# przod.net
KiCad netlist of a schematic drawn in EAGLE
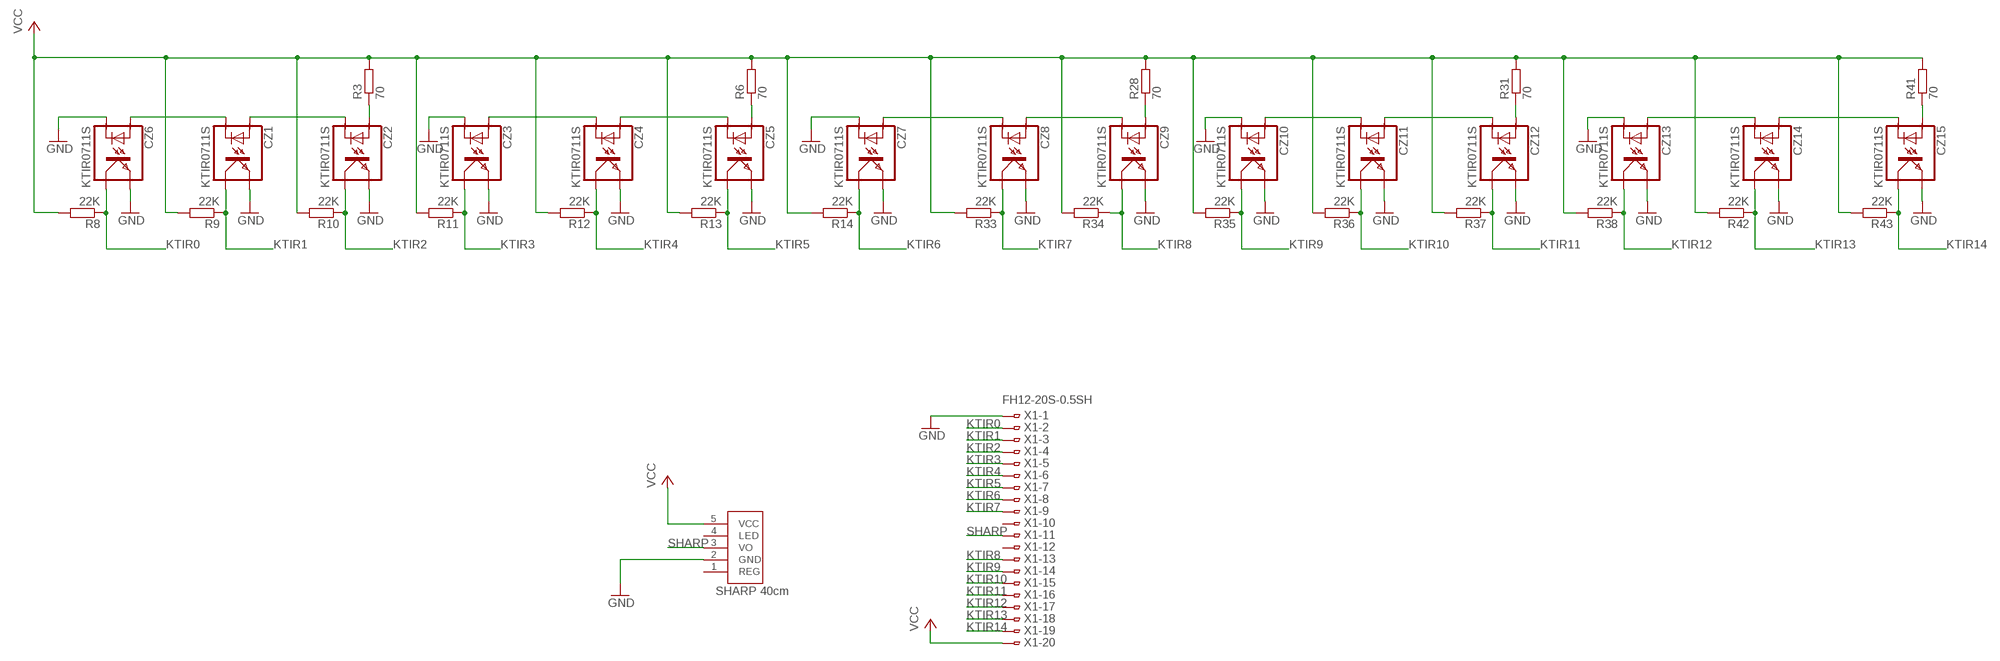
[diagram p0: schematic, sheet 1]

(export (version "E")
  (design (tool "Eeschema 10.0.6"))
  (components
    (comp (ref "CZ1")
      (value "KTIR0711S")
      (footprint "eagle-import:TOP")
      (libsource (lib "eagle-import") (part "KTIR0711S"))
    )
    (comp (ref "CZ2")
      (value "KTIR0711S")
      (footprint "eagle-import:TOP")
      (libsource (lib "eagle-import") (part "KTIR0711S"))
    )
    (comp (ref "CZ3")
      (value "KTIR0711S")
      (footprint "eagle-import:TOP")
      (libsource (lib "eagle-import") (part "KTIR0711S"))
    )
    (comp (ref "CZ4")
      (value "KTIR0711S")
      (footprint "eagle-import:TOP")
      (libsource (lib "eagle-import") (part "KTIR0711S"))
    )
    (comp (ref "CZ5")
      (value "KTIR0711S")
      (footprint "eagle-import:TOP")
      (libsource (lib "eagle-import") (part "KTIR0711S"))
    )
    (comp (ref "CZ6")
      (value "KTIR0711S")
      (footprint "eagle-import:TOP")
      (libsource (lib "eagle-import") (part "KTIR0711S"))
    )
    (comp (ref "CZ7")
      (value "KTIR0711S")
      (footprint "eagle-import:TOP")
      (libsource (lib "eagle-import") (part "KTIR0711S"))
    )
    (comp (ref "CZ8")
      (value "KTIR0711S")
      (footprint "eagle-import:TOP")
      (libsource (lib "eagle-import") (part "KTIR0711S"))
    )
    (comp (ref "CZ9")
      (value "KTIR0711S")
      (footprint "eagle-import:TOP")
      (libsource (lib "eagle-import") (part "KTIR0711S"))
    )
    (comp (ref "CZ10")
      (value "KTIR0711S")
      (footprint "eagle-import:TOP")
      (libsource (lib "eagle-import") (part "KTIR0711S"))
    )
    (comp (ref "CZ11")
      (value "KTIR0711S")
      (footprint "eagle-import:TOP")
      (libsource (lib "eagle-import") (part "KTIR0711S"))
    )
    (comp (ref "CZ12")
      (value "KTIR0711S")
      (footprint "eagle-import:TOP")
      (libsource (lib "eagle-import") (part "KTIR0711S"))
    )
    (comp (ref "CZ13")
      (value "KTIR0711S")
      (footprint "eagle-import:TOP")
      (libsource (lib "eagle-import") (part "KTIR0711S"))
    )
    (comp (ref "CZ14")
      (value "KTIR0711S")
      (footprint "eagle-import:TOP")
      (libsource (lib "eagle-import") (part "KTIR0711S"))
    )
    (comp (ref "CZ15")
      (value "KTIR0711S")
      (footprint "eagle-import:TOP")
      (libsource (lib "eagle-import") (part "KTIR0711S"))
    )
    (comp (ref "R3")
      (value "70")
      (footprint "eagle-import:R0805")
      (libsource (lib "eagle-import") (part "R-EU_R0805"))
    )
    (comp (ref "R6")
      (value "70")
      (footprint "eagle-import:R0805")
      (libsource (lib "eagle-import") (part "R-EU_R0805"))
    )
    (comp (ref "R8")
      (value "22K")
      (footprint "eagle-import:R0805")
      (libsource (lib "eagle-import") (part "R-EU_R0805"))
    )
    (comp (ref "R9")
      (value "22K")
      (footprint "eagle-import:R0805")
      (libsource (lib "eagle-import") (part "R-EU_R0805"))
    )
    (comp (ref "R10")
      (value "22K")
      (footprint "eagle-import:R0805")
      (libsource (lib "eagle-import") (part "R-EU_R0805"))
    )
    (comp (ref "R11")
      (value "22K")
      (footprint "eagle-import:R0805")
      (libsource (lib "eagle-import") (part "R-EU_R0805"))
    )
    (comp (ref "R12")
      (value "22K")
      (footprint "eagle-import:R0805")
      (libsource (lib "eagle-import") (part "R-EU_R0805"))
    )
    (comp (ref "R13")
      (value "22K")
      (footprint "eagle-import:R0805")
      (libsource (lib "eagle-import") (part "R-EU_R0805"))
    )
    (comp (ref "R14")
      (value "22K")
      (footprint "eagle-import:R0805")
      (libsource (lib "eagle-import") (part "R-EU_R0805"))
    )
    (comp (ref "R28")
      (value "70")
      (footprint "eagle-import:R0805")
      (libsource (lib "eagle-import") (part "R-EU_R0805"))
    )
    (comp (ref "R31")
      (value "70")
      (footprint "eagle-import:R0805")
      (libsource (lib "eagle-import") (part "R-EU_R0805"))
    )
    (comp (ref "R33")
      (value "22K")
      (footprint "eagle-import:R0805")
      (libsource (lib "eagle-import") (part "R-EU_R0805"))
    )
    (comp (ref "R34")
      (value "22K")
      (footprint "eagle-import:R0805")
      (libsource (lib "eagle-import") (part "R-EU_R0805"))
    )
    (comp (ref "R35")
      (value "22K")
      (footprint "eagle-import:R0805")
      (libsource (lib "eagle-import") (part "R-EU_R0805"))
    )
    (comp (ref "R36")
      (value "22K")
      (footprint "eagle-import:R0805")
      (libsource (lib "eagle-import") (part "R-EU_R0805"))
    )
    (comp (ref "R37")
      (value "22K")
      (footprint "eagle-import:R0805")
      (libsource (lib "eagle-import") (part "R-EU_R0805"))
    )
    (comp (ref "R38")
      (value "22K")
      (footprint "eagle-import:R0805")
      (libsource (lib "eagle-import") (part "R-EU_R0805"))
    )
    (comp (ref "R41")
      (value "70")
      (footprint "eagle-import:R0805")
      (libsource (lib "eagle-import") (part "R-EU_R0805"))
    )
    (comp (ref "R42")
      (value "22K")
      (footprint "eagle-import:R0805")
      (libsource (lib "eagle-import") (part "R-EU_R0805"))
    )
    (comp (ref "R43")
      (value "22K")
      (footprint "eagle-import:R0805")
      (libsource (lib "eagle-import") (part "R-EU_R0805"))
    )
    (comp (ref "U$1")
      (value "GP2Y0D340K")
      (footprint "eagle-import:GP2Y0D340K")
      (libsource (lib "eagle-import") (part "GP2Y0D340K"))
    )
    (comp (ref "X1")
      (value "FH12-20S-0.5SH")
      (footprint "eagle-import:FH12-20S-0.5SH")
      (fields (field (name "MPN") "FH12-20S-0.5SH(55)"))
      (libsource (lib "eagle-import") (part "FH12-20S-0.5SH"))
    )
  )
  (nets
    (net (code "1") (name "/KTIR0") (class "Default")
      (node (ref "CZ6") (pin "KOLEKTOR") (pinfunction "KOLEKTOR_KOLEKTOR") (pintype "bidirectional"))
      (node (ref "R8") (pin "1") (pinfunction "1_1") (pintype "passive"))
      (node (ref "X1") (pin "2") (pinfunction "1_2") (pintype "passive"))
    )
    (net (code "2") (name "/KTIR1") (class "Default")
      (node (ref "CZ1") (pin "KOLEKTOR") (pinfunction "KOLEKTOR_KOLEKTOR") (pintype "bidirectional"))
      (node (ref "R9") (pin "1") (pinfunction "1_1") (pintype "passive"))
      (node (ref "X1") (pin "3") (pinfunction "1_3") (pintype "passive"))
    )
    (net (code "3") (name "/KTIR2") (class "Default")
      (node (ref "CZ2") (pin "KOLEKTOR") (pinfunction "KOLEKTOR_KOLEKTOR") (pintype "bidirectional"))
      (node (ref "R10") (pin "1") (pinfunction "1_1") (pintype "passive"))
      (node (ref "X1") (pin "4") (pinfunction "1_4") (pintype "passive"))
    )
    (net (code "4") (name "/KTIR3") (class "Default")
      (node (ref "CZ3") (pin "KOLEKTOR") (pinfunction "KOLEKTOR_KOLEKTOR") (pintype "bidirectional"))
      (node (ref "R11") (pin "1") (pinfunction "1_1") (pintype "passive"))
      (node (ref "X1") (pin "5") (pinfunction "1_5") (pintype "passive"))
    )
    (net (code "5") (name "/KTIR4") (class "Default")
      (node (ref "CZ4") (pin "KOLEKTOR") (pinfunction "KOLEKTOR_KOLEKTOR") (pintype "bidirectional"))
      (node (ref "R12") (pin "1") (pinfunction "1_1") (pintype "passive"))
      (node (ref "X1") (pin "6") (pinfunction "1_6") (pintype "passive"))
    )
    (net (code "6") (name "/KTIR5") (class "Default")
      (node (ref "CZ5") (pin "KOLEKTOR") (pinfunction "KOLEKTOR_KOLEKTOR") (pintype "bidirectional"))
      (node (ref "R13") (pin "1") (pinfunction "1_1") (pintype "passive"))
      (node (ref "X1") (pin "7") (pinfunction "1_7") (pintype "passive"))
    )
    (net (code "7") (name "/KTIR6") (class "Default")
      (node (ref "CZ7") (pin "KOLEKTOR") (pinfunction "KOLEKTOR_KOLEKTOR") (pintype "bidirectional"))
      (node (ref "R14") (pin "1") (pinfunction "1_1") (pintype "passive"))
      (node (ref "X1") (pin "8") (pinfunction "1_8") (pintype "passive"))
    )
    (net (code "8") (name "/KTIR7") (class "Default")
      (node (ref "CZ8") (pin "KOLEKTOR") (pinfunction "KOLEKTOR_KOLEKTOR") (pintype "bidirectional"))
      (node (ref "R33") (pin "1") (pinfunction "1_1") (pintype "passive"))
      (node (ref "X1") (pin "9") (pinfunction "1_9") (pintype "passive"))
    )
    (net (code "9") (name "/KTIR8") (class "Default")
      (node (ref "CZ9") (pin "KOLEKTOR") (pinfunction "KOLEKTOR_KOLEKTOR") (pintype "bidirectional"))
      (node (ref "R34") (pin "1") (pinfunction "1_1") (pintype "passive"))
      (node (ref "X1") (pin "13") (pinfunction "1_13") (pintype "passive"))
    )
    (net (code "10") (name "/KTIR9") (class "Default")
      (node (ref "CZ10") (pin "KOLEKTOR") (pinfunction "KOLEKTOR_KOLEKTOR") (pintype "bidirectional"))
      (node (ref "R35") (pin "1") (pinfunction "1_1") (pintype "passive"))
      (node (ref "X1") (pin "14") (pinfunction "1_14") (pintype "passive"))
    )
    (net (code "11") (name "/KTIR10") (class "Default")
      (node (ref "CZ11") (pin "KOLEKTOR") (pinfunction "KOLEKTOR_KOLEKTOR") (pintype "bidirectional"))
      (node (ref "R36") (pin "1") (pinfunction "1_1") (pintype "passive"))
      (node (ref "X1") (pin "15") (pinfunction "1_15") (pintype "passive"))
    )
    (net (code "12") (name "/KTIR11") (class "Default")
      (node (ref "CZ12") (pin "KOLEKTOR") (pinfunction "KOLEKTOR_KOLEKTOR") (pintype "bidirectional"))
      (node (ref "R37") (pin "1") (pinfunction "1_1") (pintype "passive"))
      (node (ref "X1") (pin "16") (pinfunction "1_16") (pintype "passive"))
    )
    (net (code "13") (name "/KTIR12") (class "Default")
      (node (ref "CZ13") (pin "KOLEKTOR") (pinfunction "KOLEKTOR_KOLEKTOR") (pintype "bidirectional"))
      (node (ref "R38") (pin "1") (pinfunction "1_1") (pintype "passive"))
      (node (ref "X1") (pin "17") (pinfunction "1_17") (pintype "passive"))
    )
    (net (code "14") (name "/KTIR13") (class "Default")
      (node (ref "CZ14") (pin "KOLEKTOR") (pinfunction "KOLEKTOR_KOLEKTOR") (pintype "bidirectional"))
      (node (ref "R42") (pin "1") (pinfunction "1_1") (pintype "passive"))
      (node (ref "X1") (pin "18") (pinfunction "1_18") (pintype "passive"))
    )
    (net (code "15") (name "/KTIR14") (class "Default")
      (node (ref "CZ15") (pin "KOLEKTOR") (pinfunction "KOLEKTOR_KOLEKTOR") (pintype "bidirectional"))
      (node (ref "R43") (pin "1") (pinfunction "1_1") (pintype "passive"))
      (node (ref "X1") (pin "19") (pinfunction "1_19") (pintype "passive"))
    )
    (net (code "16") (name "/SHARP") (class "Default")
      (node (ref "U$1") (pin "3") (pinfunction "VO_3") (pintype "bidirectional"))
      (node (ref "X1") (pin "11") (pinfunction "1_11") (pintype "passive"))
    )
    (net (code "17") (name "GND") (class "Default")
      (node (ref "CZ1") (pin "EMITER") (pinfunction "EMITER_EMITER") (pintype "bidirectional"))
      (node (ref "CZ10") (pin "EMITER") (pinfunction "EMITER_EMITER") (pintype "bidirectional"))
      (node (ref "CZ10") (pin "KATODA") (pinfunction "KATODA_KATODA") (pintype "passive"))
      (node (ref "CZ11") (pin "EMITER") (pinfunction "EMITER_EMITER") (pintype "bidirectional"))
      (node (ref "CZ12") (pin "EMITER") (pinfunction "EMITER_EMITER") (pintype "bidirectional"))
      (node (ref "CZ13") (pin "EMITER") (pinfunction "EMITER_EMITER") (pintype "bidirectional"))
      (node (ref "CZ13") (pin "KATODA") (pinfunction "KATODA_KATODA") (pintype "passive"))
      (node (ref "CZ14") (pin "EMITER") (pinfunction "EMITER_EMITER") (pintype "bidirectional"))
      (node (ref "CZ15") (pin "EMITER") (pinfunction "EMITER_EMITER") (pintype "bidirectional"))
      (node (ref "CZ2") (pin "EMITER") (pinfunction "EMITER_EMITER") (pintype "bidirectional"))
      (node (ref "CZ3") (pin "EMITER") (pinfunction "EMITER_EMITER") (pintype "bidirectional"))
      (node (ref "CZ3") (pin "KATODA") (pinfunction "KATODA_KATODA") (pintype "passive"))
      (node (ref "CZ4") (pin "EMITER") (pinfunction "EMITER_EMITER") (pintype "bidirectional"))
      (node (ref "CZ5") (pin "EMITER") (pinfunction "EMITER_EMITER") (pintype "bidirectional"))
      (node (ref "CZ6") (pin "EMITER") (pinfunction "EMITER_EMITER") (pintype "bidirectional"))
      (node (ref "CZ6") (pin "KATODA") (pinfunction "KATODA_KATODA") (pintype "passive"))
      (node (ref "CZ7") (pin "EMITER") (pinfunction "EMITER_EMITER") (pintype "bidirectional"))
      (node (ref "CZ7") (pin "KATODA") (pinfunction "KATODA_KATODA") (pintype "passive"))
      (node (ref "CZ8") (pin "EMITER") (pinfunction "EMITER_EMITER") (pintype "bidirectional"))
      (node (ref "CZ9") (pin "EMITER") (pinfunction "EMITER_EMITER") (pintype "bidirectional"))
      (node (ref "U$1") (pin "2") (pinfunction "GND_2") (pintype "bidirectional"))
      (node (ref "X1") (pin "1") (pinfunction "1_1") (pintype "passive"))
    )
    (net (code "18") (name "Net-(CZ1-PadANODA)") (class "Default")
      (node (ref "CZ1") (pin "ANODA") (pinfunction "ANODA_ANODA") (pintype "passive"))
      (node (ref "CZ2") (pin "KATODA") (pinfunction "KATODA_KATODA") (pintype "passive"))
    )
    (net (code "19") (name "Net-(CZ1-PadKATODA)") (class "Default")
      (node (ref "CZ1") (pin "KATODA") (pinfunction "KATODA_KATODA") (pintype "passive"))
      (node (ref "CZ6") (pin "ANODA") (pinfunction "ANODA_ANODA") (pintype "passive"))
    )
    (net (code "20") (name "Net-(CZ2-PadANODA)") (class "Default")
      (node (ref "CZ2") (pin "ANODA") (pinfunction "ANODA_ANODA") (pintype "passive"))
      (node (ref "R3") (pin "1") (pinfunction "1_1") (pintype "passive"))
    )
    (net (code "21") (name "Net-(CZ3-PadANODA)") (class "Default")
      (node (ref "CZ3") (pin "ANODA") (pinfunction "ANODA_ANODA") (pintype "passive"))
      (node (ref "CZ4") (pin "KATODA") (pinfunction "KATODA_KATODA") (pintype "passive"))
    )
    (net (code "22") (name "Net-(CZ4-PadANODA)") (class "Default")
      (node (ref "CZ4") (pin "ANODA") (pinfunction "ANODA_ANODA") (pintype "passive"))
      (node (ref "CZ5") (pin "KATODA") (pinfunction "KATODA_KATODA") (pintype "passive"))
    )
    (net (code "23") (name "Net-(CZ5-PadANODA)") (class "Default")
      (node (ref "CZ5") (pin "ANODA") (pinfunction "ANODA_ANODA") (pintype "passive"))
      (node (ref "R6") (pin "1") (pinfunction "1_1") (pintype "passive"))
    )
    (net (code "24") (name "Net-(CZ7-PadANODA)") (class "Default")
      (node (ref "CZ7") (pin "ANODA") (pinfunction "ANODA_ANODA") (pintype "passive"))
      (node (ref "CZ8") (pin "KATODA") (pinfunction "KATODA_KATODA") (pintype "passive"))
    )
    (net (code "25") (name "Net-(CZ8-PadANODA)") (class "Default")
      (node (ref "CZ8") (pin "ANODA") (pinfunction "ANODA_ANODA") (pintype "passive"))
      (node (ref "CZ9") (pin "KATODA") (pinfunction "KATODA_KATODA") (pintype "passive"))
    )
    (net (code "26") (name "Net-(CZ9-PadANODA)") (class "Default")
      (node (ref "CZ9") (pin "ANODA") (pinfunction "ANODA_ANODA") (pintype "passive"))
      (node (ref "R28") (pin "1") (pinfunction "1_1") (pintype "passive"))
    )
    (net (code "27") (name "Net-(CZ10-PadANODA)") (class "Default")
      (node (ref "CZ10") (pin "ANODA") (pinfunction "ANODA_ANODA") (pintype "passive"))
      (node (ref "CZ11") (pin "KATODA") (pinfunction "KATODA_KATODA") (pintype "passive"))
    )
    (net (code "28") (name "Net-(CZ11-PadANODA)") (class "Default")
      (node (ref "CZ11") (pin "ANODA") (pinfunction "ANODA_ANODA") (pintype "passive"))
      (node (ref "CZ12") (pin "KATODA") (pinfunction "KATODA_KATODA") (pintype "passive"))
    )
    (net (code "29") (name "Net-(CZ12-PadANODA)") (class "Default")
      (node (ref "CZ12") (pin "ANODA") (pinfunction "ANODA_ANODA") (pintype "passive"))
      (node (ref "R31") (pin "1") (pinfunction "1_1") (pintype "passive"))
    )
    (net (code "30") (name "Net-(CZ13-PadANODA)") (class "Default")
      (node (ref "CZ13") (pin "ANODA") (pinfunction "ANODA_ANODA") (pintype "passive"))
      (node (ref "CZ14") (pin "KATODA") (pinfunction "KATODA_KATODA") (pintype "passive"))
    )
    (net (code "31") (name "Net-(CZ14-PadANODA)") (class "Default")
      (node (ref "CZ14") (pin "ANODA") (pinfunction "ANODA_ANODA") (pintype "passive"))
      (node (ref "CZ15") (pin "KATODA") (pinfunction "KATODA_KATODA") (pintype "passive"))
    )
    (net (code "32") (name "Net-(CZ15-PadANODA)") (class "Default")
      (node (ref "CZ15") (pin "ANODA") (pinfunction "ANODA_ANODA") (pintype "passive"))
      (node (ref "R41") (pin "1") (pinfunction "1_1") (pintype "passive"))
    )
    (net (code "33") (name "VCC") (class "Default")
      (node (ref "R10") (pin "2") (pinfunction "2_2") (pintype "passive"))
      (node (ref "R11") (pin "2") (pinfunction "2_2") (pintype "passive"))
      (node (ref "R12") (pin "2") (pinfunction "2_2") (pintype "passive"))
      (node (ref "R13") (pin "2") (pinfunction "2_2") (pintype "passive"))
      (node (ref "R14") (pin "2") (pinfunction "2_2") (pintype "passive"))
      (node (ref "R28") (pin "2") (pinfunction "2_2") (pintype "passive"))
      (node (ref "R3") (pin "2") (pinfunction "2_2") (pintype "passive"))
      (node (ref "R31") (pin "2") (pinfunction "2_2") (pintype "passive"))
      (node (ref "R33") (pin "2") (pinfunction "2_2") (pintype "passive"))
      (node (ref "R34") (pin "2") (pinfunction "2_2") (pintype "passive"))
      (node (ref "R35") (pin "2") (pinfunction "2_2") (pintype "passive"))
      (node (ref "R36") (pin "2") (pinfunction "2_2") (pintype "passive"))
      (node (ref "R37") (pin "2") (pinfunction "2_2") (pintype "passive"))
      (node (ref "R38") (pin "2") (pinfunction "2_2") (pintype "passive"))
      (node (ref "R41") (pin "2") (pinfunction "2_2") (pintype "passive"))
      (node (ref "R42") (pin "2") (pinfunction "2_2") (pintype "passive"))
      (node (ref "R43") (pin "2") (pinfunction "2_2") (pintype "passive"))
      (node (ref "R6") (pin "2") (pinfunction "2_2") (pintype "passive"))
      (node (ref "R8") (pin "2") (pinfunction "2_2") (pintype "passive"))
      (node (ref "R9") (pin "2") (pinfunction "2_2") (pintype "passive"))
      (node (ref "U$1") (pin "5") (pinfunction "VCC_5") (pintype "bidirectional"))
      (node (ref "X1") (pin "20") (pinfunction "1_20") (pintype "passive"))
    )
    (net (code "34") (name "unconnected-(U$1-LED-Pad4)") (class "Default")
      (node (ref "U$1") (pin "4") (pinfunction "LED_4") (pintype "bidirectional"))
    )
    (net (code "35") (name "unconnected-(U$1-REG-Pad1)") (class "Default")
      (node (ref "U$1") (pin "1") (pinfunction "REG_1") (pintype "bidirectional"))
    )
    (net (code "36") (name "unconnected-(X1B-1-Pad10)") (class "Default")
      (node (ref "X1") (pin "10") (pinfunction "1_10") (pintype "passive"))
    )
    (net (code "37") (name "unconnected-(X1D-1-Pad12)") (class "Default")
      (node (ref "X1") (pin "12") (pinfunction "1_12") (pintype "passive"))
    )
  )
)
